# RTM_Connectors.net
KiCad netlist of a schematic drawn in Altium Designer
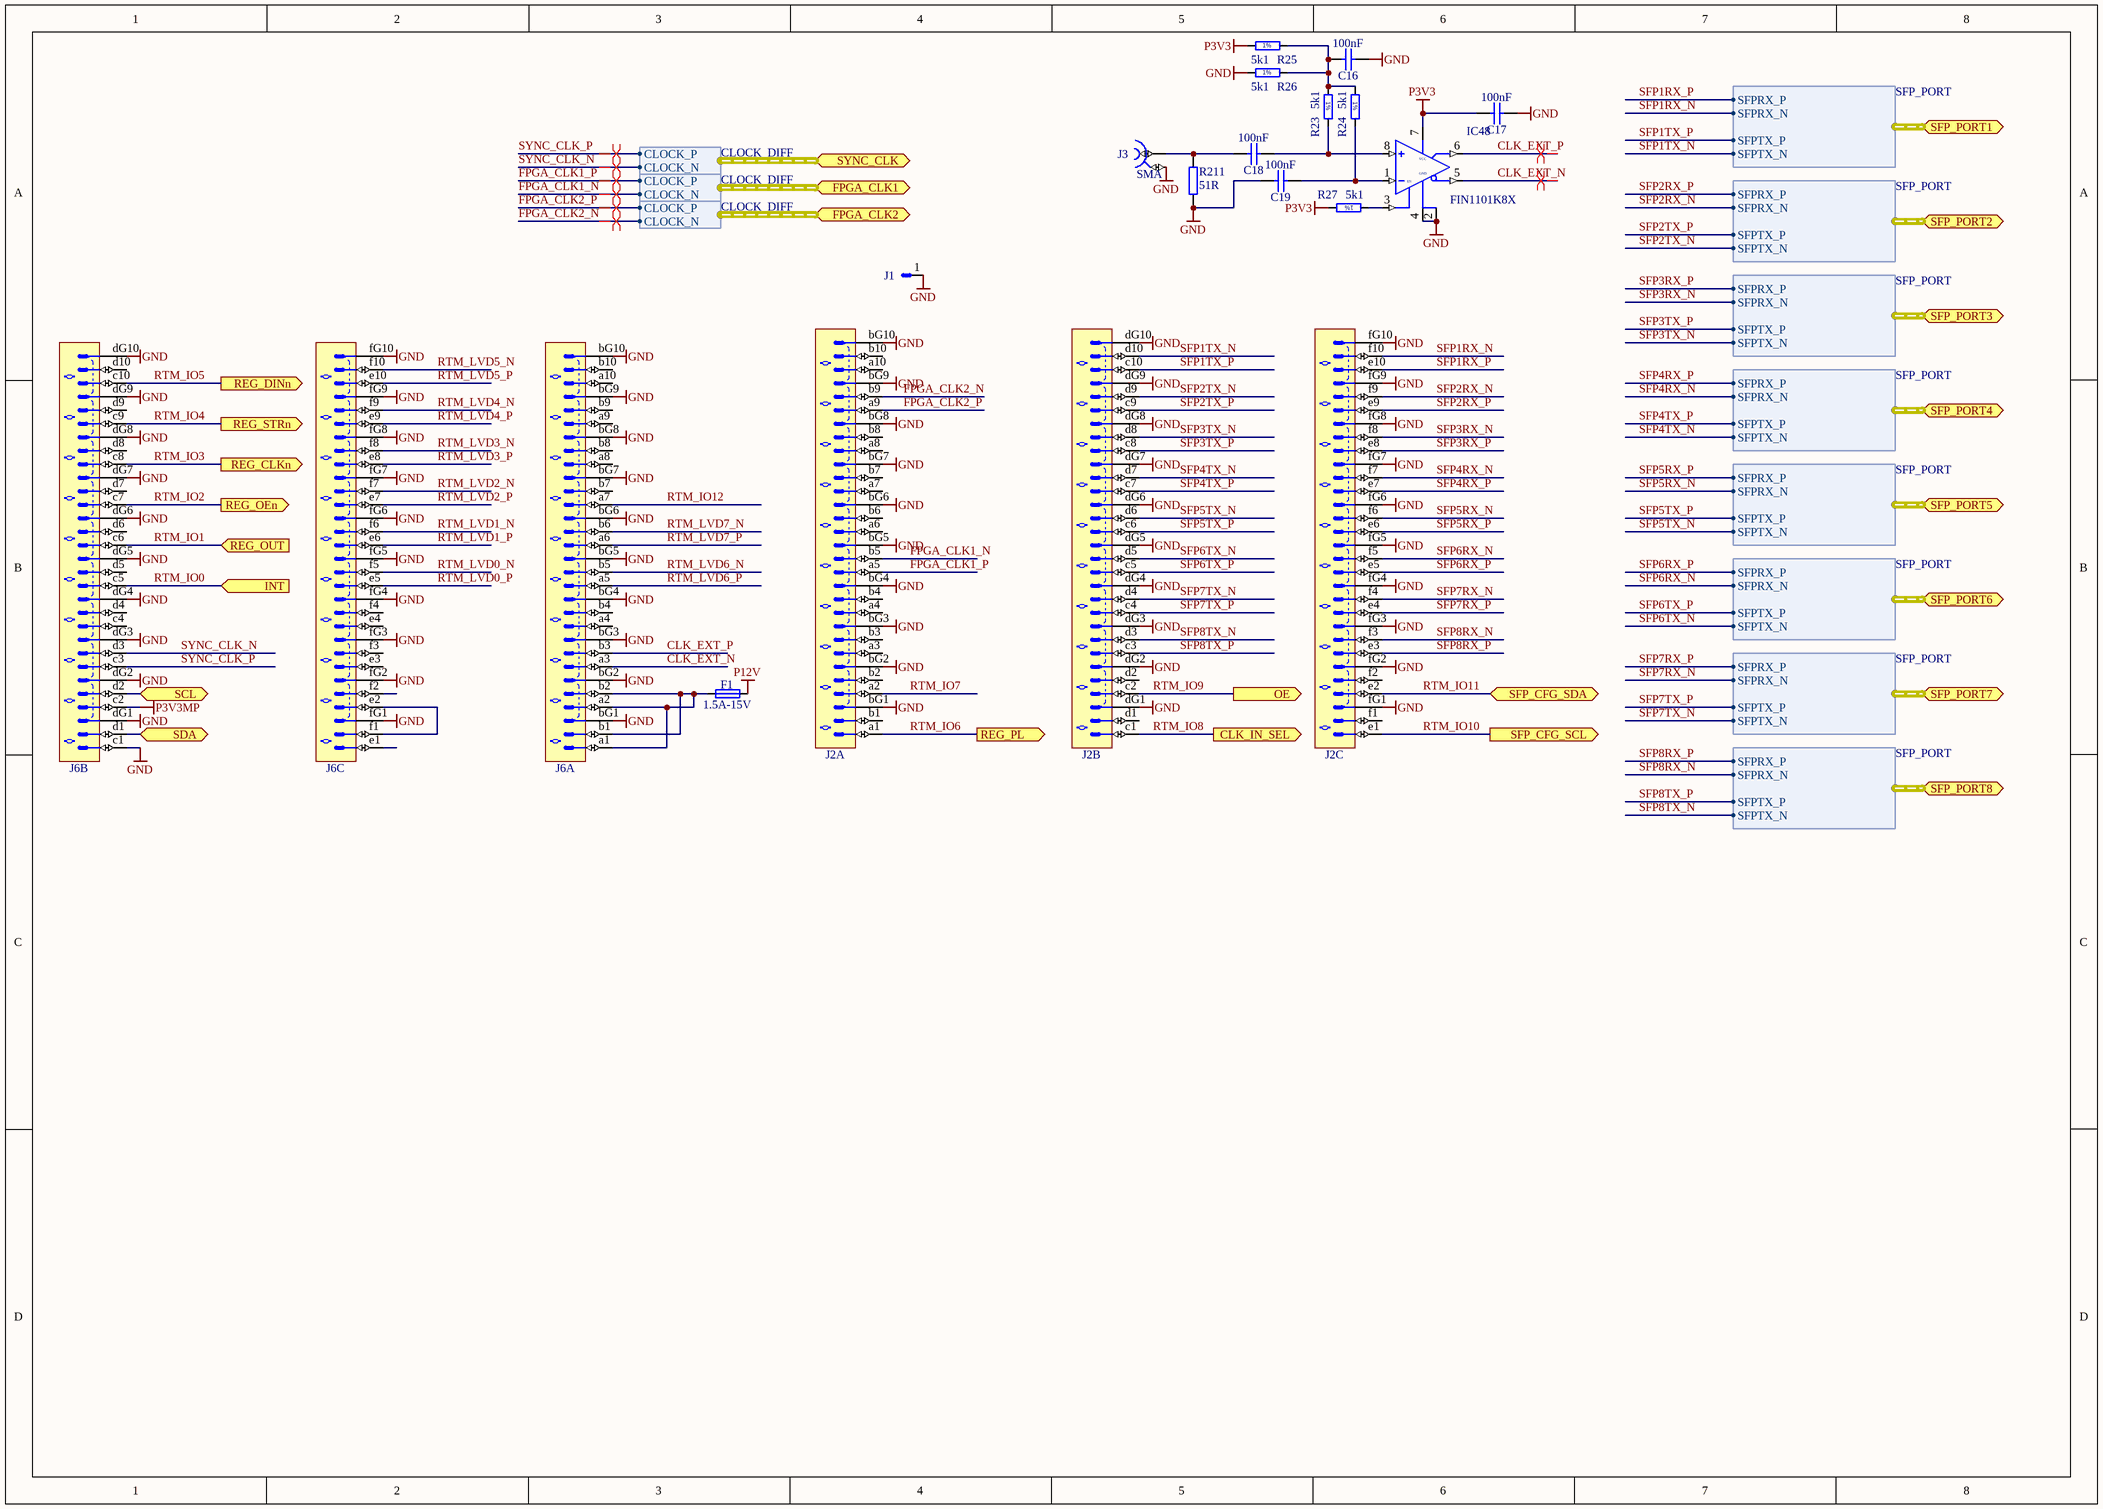
[diagram p0: RTM_Connectors.SchDoc]

(export (version "E")
  (design (tool "Eeschema 10.0.6"))
  (components
    (comp (ref "C16")
      (value "100nF")
      (footprint "CAPC1005X55N")
      (description "Non-polarised capacitor")
      (fields
        (field (name "PART NUMBER") "CC0402_100NF_16V_10%_X7R")
        (field (name "VOLTAGE") "16V")
        (field (name "AUTHOR") "CERN DEM JLC")
      )
      (libsource (lib "Capacitors") (part "Capacitor - non polarized"))
    )
    (comp (ref "C17")
      (value "100nF")
      (footprint "CAPC1005X55N")
      (description "Non-polarised capacitor")
      (fields
        (field (name "PART NUMBER") "CC0402_100NF_16V_10%_X7R")
        (field (name "VOLTAGE") "16V")
        (field (name "AUTHOR") "CERN DEM JLC")
      )
      (libsource (lib "Capacitors") (part "Capacitor - non polarized"))
    )
    (comp (ref "C18")
      (value "100nF")
      (footprint "CAPC1005X55N")
      (description "Non-polarised capacitor")
      (fields
        (field (name "PART NUMBER") "CC0402_100NF_16V_10%_X7R")
        (field (name "VOLTAGE") "16V")
        (field (name "AUTHOR") "CERN DEM JLC")
      )
      (libsource (lib "Capacitors") (part "Capacitor - non polarized"))
    )
    (comp (ref "C19")
      (value "100nF")
      (footprint "CAPC1005X55N")
      (description "Non-polarised capacitor")
      (fields
        (field (name "PART NUMBER") "CC0402_100NF_16V_10%_X7R")
        (field (name "VOLTAGE") "16V")
        (field (name "AUTHOR") "CERN DEM JLC")
      )
      (libsource (lib "Capacitors") (part "Capacitor - non polarized"))
    )
    (comp (ref "F1")
      (value "1.5A-15V")
      (footprint "FUSR_TYCO_SMD150F-2")
      (description "Fuse")
      (fields
        (field (name "PART NUMBER") "FUSR_TYCO_SMD150F-2")
        (field (name "MANUFACTURER") "TYCO ELECTRONICS")
        (field (name "AUTHOR") "CERN DEM JLC")
      )
      (libsource (lib "Eletro-mechanical") (part "Fuse"))
    )
    (comp (ref "IC48")
      (value "FIN1101K8X")
      (footprint "US8")
      (description "LVDS TO LVDS repeater3.3V")
      (libsource (lib "AMC_FMC_Carrier") (part "IFC_FIN1101K8X"))
    )
    (comp (ref "J1")
      (value "~")
      (footprint "TYCO_1469265-1")
      (description "Single Pin Male")
      (fields (field (name "PART NUMBER") "TYCO_1469265-1"))
      (libsource (lib "Connectors") (part "Single Pin Male"))
    )
    (comp (ref "J2")
      (value "~")
      (footprint "TYCO_6469183-1")
      (description "Connector 60 ATCA Male 30 Pairs (60 Signals) + 3x10 Ground")
      (fields (field (name "PART NUMBER") "TYCO_6469183-1"))
      (libsource (lib "Connectors") (part "Connector ATCA 60+30 Male"))
    )
    (comp (ref "J3")
      (value "SMA")
      (footprint "HUBER-SUHNER_85 SMA-50-0-101/111 NE")
      (fields
        (field (name "PART NUMBER") "HUBER-SUHNER_85_SMA-50-0-101/111_NE")
        (field (name "MANUFACTURER") "HUBER+SUHNER")
        (field (name "MANUFACTURER PART NUMBER") "85_SMA-50-0-101/111_NE")
        (field (name "AUTHOR") "CERN DEM JLC")
      )
      (libsource (lib "Connectors") (part "Coax_1Female_1Shield"))
    )
    (comp (ref "J6")
      (value "~")
      (footprint "TYCO_6469183-1")
      (description "Connector 60 ATCA Male 30 Pairs (60 Signals) + 3x10 Ground")
      (fields (field (name "PART NUMBER") "TYCO_6469183-1"))
      (libsource (lib "Connectors") (part "Connector ATCA 60+30 Male"))
    )
    (comp (ref "R23")
      (value "5k1")
      (footprint "RESC1608X55N")
      (description "Resistor - 1%")
      (fields
        (field (name "PART NUMBER") "R0603_5K1_1%_0.1W_100PPM")
        (field (name "POWER") "0.1W")
        (field (name "AUTHOR") "CERN DEM JLC")
      )
      (libsource (lib "Resistors") (part "Resistor - 1%"))
    )
    (comp (ref "R24")
      (value "5k1")
      (footprint "RESC1608X55N")
      (description "Resistor - 1%")
      (fields
        (field (name "PART NUMBER") "R0603_5K1_1%_0.1W_100PPM")
        (field (name "POWER") "0.1W")
        (field (name "AUTHOR") "CERN DEM JLC")
      )
      (libsource (lib "Resistors") (part "Resistor - 1%"))
    )
    (comp (ref "R25")
      (value "5k1")
      (footprint "RESC1608X55N")
      (description "Resistor - 1%")
      (fields
        (field (name "PART NUMBER") "R0603_5K1_1%_0.1W_100PPM")
        (field (name "POWER") "0.1W")
        (field (name "AUTHOR") "CERN DEM JLC")
      )
      (libsource (lib "Resistors") (part "Resistor - 1%"))
    )
    (comp (ref "R26")
      (value "5k1")
      (footprint "RESC1608X55N")
      (description "Resistor - 1%")
      (fields
        (field (name "PART NUMBER") "R0603_5K1_1%_0.1W_100PPM")
        (field (name "POWER") "0.1W")
        (field (name "AUTHOR") "CERN DEM JLC")
      )
      (libsource (lib "Resistors") (part "Resistor - 1%"))
    )
    (comp (ref "R27")
      (value "5k1")
      (footprint "RESC1608X55N")
      (description "Resistor - 1%")
      (fields
        (field (name "PART NUMBER") "R0603_5K1_1%_0.1W_100PPM")
        (field (name "POWER") "0.1W")
        (field (name "AUTHOR") "CERN DEM JLC")
      )
      (libsource (lib "Resistors") (part "Resistor - 1%"))
    )
    (comp (ref "R211")
      (value "51R")
      (footprint "0402R")
      (description "SMD Resistor")
      (libsource (lib "LIBRARY_SCH") (part "RES_0402"))
    )
  )
  (nets
    (net (code "3") (name "/CLK_EXT_N") (class "Default")
      (node (ref "IC48") (pin "5") (pinfunction "~{Q}_5") (pintype "output"))
      (node (ref "J6") (pin "a3") (pinfunction "a3_a3") (pintype "bidirectional"))
    )
    (net (code "4") (name "/CLK_EXT_P") (class "Default")
      (node (ref "IC48") (pin "6") (pinfunction "Q_6") (pintype "output"))
      (node (ref "J6") (pin "b3") (pinfunction "b3_b3") (pintype "bidirectional"))
    )
    (net (code "5") (name "/FPGA_CLK1_N") (class "Default")
      (node (ref "J2") (pin "b5") (pinfunction "b5_b5") (pintype "bidirectional"))
    )
    (net (code "6") (name "/FPGA_CLK1_P") (class "Default")
      (node (ref "J2") (pin "a5") (pinfunction "a5_a5") (pintype "bidirectional"))
    )
    (net (code "7") (name "/FPGA_CLK2_N") (class "Default")
      (node (ref "J2") (pin "b9") (pinfunction "b9_b9") (pintype "bidirectional"))
    )
    (net (code "8") (name "/FPGA_CLK2_P") (class "Default")
      (node (ref "J2") (pin "a9") (pinfunction "a9_a9") (pintype "bidirectional"))
    )
    (net (code "9") (name "/RTM_IO0") (class "Default")
      (node (ref "J6") (pin "c5") (pinfunction "c5_c5") (pintype "bidirectional"))
    )
    (net (code "10") (name "/RTM_IO1") (class "Default")
      (node (ref "J6") (pin "c6") (pinfunction "c6_c6") (pintype "bidirectional"))
    )
    (net (code "11") (name "/RTM_IO2") (class "Default")
      (node (ref "J6") (pin "c7") (pinfunction "c7_c7") (pintype "bidirectional"))
    )
    (net (code "12") (name "/RTM_IO3") (class "Default")
      (node (ref "J6") (pin "c8") (pinfunction "c8_c8") (pintype "bidirectional"))
    )
    (net (code "13") (name "/RTM_IO4") (class "Default")
      (node (ref "J6") (pin "c9") (pinfunction "c9_c9") (pintype "bidirectional"))
    )
    (net (code "14") (name "/RTM_IO5") (class "Default")
      (node (ref "J6") (pin "c10") (pinfunction "c10_c10") (pintype "bidirectional"))
    )
    (net (code "15") (name "/RTM_IO6") (class "Default")
      (node (ref "J2") (pin "a1") (pinfunction "a1_a1") (pintype "bidirectional"))
    )
    (net (code "16") (name "/RTM_IO7") (class "Default")
      (node (ref "J2") (pin "a2") (pinfunction "a2_a2") (pintype "bidirectional"))
    )
    (net (code "17") (name "/RTM_IO8") (class "Default")
      (node (ref "J2") (pin "c1") (pinfunction "c1_c1") (pintype "bidirectional"))
    )
    (net (code "18") (name "/RTM_IO9") (class "Default")
      (node (ref "J2") (pin "c2") (pinfunction "c2_c2") (pintype "bidirectional"))
    )
    (net (code "19") (name "/RTM_IO10") (class "Default")
      (node (ref "J2") (pin "e1") (pinfunction "e1_e1") (pintype "bidirectional"))
    )
    (net (code "20") (name "/RTM_IO11") (class "Default")
      (node (ref "J2") (pin "e2") (pinfunction "e2_e2") (pintype "bidirectional"))
    )
    (net (code "21") (name "/RTM_IO12") (class "Default")
      (node (ref "J6") (pin "a7") (pinfunction "a7_a7") (pintype "bidirectional"))
    )
    (net (code "22") (name "/RTM_LVD0_N") (class "Default")
      (node (ref "J6") (pin "f5") (pinfunction "f5_f5") (pintype "bidirectional"))
    )
    (net (code "23") (name "/RTM_LVD0_P") (class "Default")
      (node (ref "J6") (pin "e5") (pinfunction "e5_e5") (pintype "bidirectional"))
    )
    (net (code "24") (name "/RTM_LVD1_N") (class "Default")
      (node (ref "J6") (pin "f6") (pinfunction "f6_f6") (pintype "bidirectional"))
    )
    (net (code "25") (name "/RTM_LVD1_P") (class "Default")
      (node (ref "J6") (pin "e6") (pinfunction "e6_e6") (pintype "bidirectional"))
    )
    (net (code "26") (name "/RTM_LVD2_N") (class "Default")
      (node (ref "J6") (pin "f7") (pinfunction "f7_f7") (pintype "bidirectional"))
    )
    (net (code "27") (name "/RTM_LVD2_P") (class "Default")
      (node (ref "J6") (pin "e7") (pinfunction "e7_e7") (pintype "bidirectional"))
    )
    (net (code "28") (name "/RTM_LVD3_N") (class "Default")
      (node (ref "J6") (pin "f8") (pinfunction "f8_f8") (pintype "bidirectional"))
    )
    (net (code "29") (name "/RTM_LVD3_P") (class "Default")
      (node (ref "J6") (pin "e8") (pinfunction "e8_e8") (pintype "bidirectional"))
    )
    (net (code "30") (name "/RTM_LVD4_N") (class "Default")
      (node (ref "J6") (pin "f9") (pinfunction "f9_f9") (pintype "bidirectional"))
    )
    (net (code "31") (name "/RTM_LVD4_P") (class "Default")
      (node (ref "J6") (pin "e9") (pinfunction "e9_e9") (pintype "bidirectional"))
    )
    (net (code "32") (name "/RTM_LVD5_N") (class "Default")
      (node (ref "J6") (pin "f10") (pinfunction "f10_f10") (pintype "bidirectional"))
    )
    (net (code "33") (name "/RTM_LVD5_P") (class "Default")
      (node (ref "J6") (pin "e10") (pinfunction "e10_e10") (pintype "bidirectional"))
    )
    (net (code "34") (name "/RTM_LVD6_N") (class "Default")
      (node (ref "J6") (pin "b5") (pinfunction "b5_b5") (pintype "bidirectional"))
    )
    (net (code "35") (name "/RTM_LVD6_P") (class "Default")
      (node (ref "J6") (pin "a5") (pinfunction "a5_a5") (pintype "bidirectional"))
    )
    (net (code "36") (name "/RTM_LVD7_N") (class "Default")
      (node (ref "J6") (pin "b6") (pinfunction "b6_b6") (pintype "bidirectional"))
    )
    (net (code "37") (name "/RTM_LVD7_P") (class "Default")
      (node (ref "J6") (pin "a6") (pinfunction "a6_a6") (pintype "bidirectional"))
    )
    (net (code "38") (name "/SCL") (class "Default")
      (node (ref "J6") (pin "d2") (pinfunction "d2_d2") (pintype "bidirectional"))
    )
    (net (code "39") (name "/SDA") (class "Default")
      (node (ref "J6") (pin "d1") (pinfunction "d1_d1") (pintype "bidirectional"))
    )
    (net (code "40") (name "/SFP1RX_N") (class "Default")
      (node (ref "J2") (pin "f10") (pinfunction "f10_f10") (pintype "bidirectional"))
    )
    (net (code "41") (name "/SFP1RX_P") (class "Default")
      (node (ref "J2") (pin "e10") (pinfunction "e10_e10") (pintype "bidirectional"))
    )
    (net (code "42") (name "/SFP1TX_N") (class "Default")
      (node (ref "J2") (pin "d10") (pinfunction "d10_d10") (pintype "bidirectional"))
    )
    (net (code "43") (name "/SFP1TX_P") (class "Default")
      (node (ref "J2") (pin "c10") (pinfunction "c10_c10") (pintype "bidirectional"))
    )
    (net (code "44") (name "/SFP2RX_N") (class "Default")
      (node (ref "J2") (pin "f9") (pinfunction "f9_f9") (pintype "bidirectional"))
    )
    (net (code "45") (name "/SFP2RX_P") (class "Default")
      (node (ref "J2") (pin "e9") (pinfunction "e9_e9") (pintype "bidirectional"))
    )
    (net (code "46") (name "/SFP2TX_N") (class "Default")
      (node (ref "J2") (pin "d9") (pinfunction "d9_d9") (pintype "bidirectional"))
    )
    (net (code "47") (name "/SFP2TX_P") (class "Default")
      (node (ref "J2") (pin "c9") (pinfunction "c9_c9") (pintype "bidirectional"))
    )
    (net (code "48") (name "/SFP3RX_N") (class "Default")
      (node (ref "J2") (pin "f8") (pinfunction "f8_f8") (pintype "bidirectional"))
    )
    (net (code "49") (name "/SFP3RX_P") (class "Default")
      (node (ref "J2") (pin "e8") (pinfunction "e8_e8") (pintype "bidirectional"))
    )
    (net (code "50") (name "/SFP3TX_N") (class "Default")
      (node (ref "J2") (pin "d8") (pinfunction "d8_d8") (pintype "bidirectional"))
    )
    (net (code "51") (name "/SFP3TX_P") (class "Default")
      (node (ref "J2") (pin "c8") (pinfunction "c8_c8") (pintype "bidirectional"))
    )
    (net (code "52") (name "/SFP4RX_N") (class "Default")
      (node (ref "J2") (pin "f7") (pinfunction "f7_f7") (pintype "bidirectional"))
    )
    (net (code "53") (name "/SFP4RX_P") (class "Default")
      (node (ref "J2") (pin "e7") (pinfunction "e7_e7") (pintype "bidirectional"))
    )
    (net (code "54") (name "/SFP4TX_N") (class "Default")
      (node (ref "J2") (pin "d7") (pinfunction "d7_d7") (pintype "bidirectional"))
    )
    (net (code "55") (name "/SFP4TX_P") (class "Default")
      (node (ref "J2") (pin "c7") (pinfunction "c7_c7") (pintype "bidirectional"))
    )
    (net (code "56") (name "/SFP5RX_N") (class "Default")
      (node (ref "J2") (pin "f6") (pinfunction "f6_f6") (pintype "bidirectional"))
    )
    (net (code "57") (name "/SFP5RX_P") (class "Default")
      (node (ref "J2") (pin "e6") (pinfunction "e6_e6") (pintype "bidirectional"))
    )
    (net (code "58") (name "/SFP5TX_N") (class "Default")
      (node (ref "J2") (pin "d6") (pinfunction "d6_d6") (pintype "bidirectional"))
    )
    (net (code "59") (name "/SFP5TX_P") (class "Default")
      (node (ref "J2") (pin "c6") (pinfunction "c6_c6") (pintype "bidirectional"))
    )
    (net (code "60") (name "/SFP6RX_N") (class "Default")
      (node (ref "J2") (pin "f5") (pinfunction "f5_f5") (pintype "bidirectional"))
    )
    (net (code "61") (name "/SFP6RX_P") (class "Default")
      (node (ref "J2") (pin "e5") (pinfunction "e5_e5") (pintype "bidirectional"))
    )
    (net (code "62") (name "/SFP6TX_N") (class "Default")
      (node (ref "J2") (pin "d5") (pinfunction "d5_d5") (pintype "bidirectional"))
    )
    (net (code "63") (name "/SFP6TX_P") (class "Default")
      (node (ref "J2") (pin "c5") (pinfunction "c5_c5") (pintype "bidirectional"))
    )
    (net (code "64") (name "/SFP7RX_N") (class "Default")
      (node (ref "J2") (pin "f4") (pinfunction "f4_f4") (pintype "bidirectional"))
    )
    (net (code "65") (name "/SFP7RX_P") (class "Default")
      (node (ref "J2") (pin "e4") (pinfunction "e4_e4") (pintype "bidirectional"))
    )
    (net (code "66") (name "/SFP7TX_N") (class "Default")
      (node (ref "J2") (pin "d4") (pinfunction "d4_d4") (pintype "bidirectional"))
    )
    (net (code "67") (name "/SFP7TX_P") (class "Default")
      (node (ref "J2") (pin "c4") (pinfunction "c4_c4") (pintype "bidirectional"))
    )
    (net (code "68") (name "/SFP8RX_N") (class "Default")
      (node (ref "J2") (pin "f3") (pinfunction "f3_f3") (pintype "bidirectional"))
    )
    (net (code "69") (name "/SFP8RX_P") (class "Default")
      (node (ref "J2") (pin "e3") (pinfunction "e3_e3") (pintype "bidirectional"))
    )
    (net (code "70") (name "/SFP8TX_N") (class "Default")
      (node (ref "J2") (pin "d3") (pinfunction "d3_d3") (pintype "bidirectional"))
    )
    (net (code "71") (name "/SFP8TX_P") (class "Default")
      (node (ref "J2") (pin "c3") (pinfunction "c3_c3") (pintype "bidirectional"))
    )
    (net (code "72") (name "/SYNC_CLK_N") (class "Default")
      (node (ref "J6") (pin "d3") (pinfunction "d3_d3") (pintype "bidirectional"))
    )
    (net (code "73") (name "/SYNC_CLK_P") (class "Default")
      (node (ref "J6") (pin "c3") (pinfunction "c3_c3") (pintype "bidirectional"))
    )
    (net (code "76") (name "GND") (class "Default")
      (node (ref "C16") (pin "2") (pinfunction "2_2") (pintype "passive"))
      (node (ref "C17") (pin "2") (pinfunction "2_2") (pintype "passive"))
      (node (ref "C19") (pin "1") (pinfunction "1_1") (pintype "passive"))
      (node (ref "IC48") (pin "2") (pinfunction "GND_2") (pintype "power_in"))
      (node (ref "IC48") (pin "4") (pinfunction "GND_4") (pintype "power_in"))
      (node (ref "J1") (pin "1") (pinfunction "1_1") (pintype "bidirectional"))
      (node (ref "J2") (pin "bG1") (pinfunction "bG1_bG1") (pintype "power_in"))
      (node (ref "J2") (pin "bG10") (pinfunction "bG10_bG10") (pintype "power_in"))
      (node (ref "J2") (pin "bG2") (pinfunction "bG2_bG2") (pintype "power_in"))
      (node (ref "J2") (pin "bG3") (pinfunction "bG3_bG3") (pintype "power_in"))
      (node (ref "J2") (pin "bG4") (pinfunction "bG4_bG4") (pintype "power_in"))
      (node (ref "J2") (pin "bG5") (pinfunction "bG5_bG5") (pintype "power_in"))
      (node (ref "J2") (pin "bG6") (pinfunction "bG6_bG6") (pintype "power_in"))
      (node (ref "J2") (pin "bG7") (pinfunction "bG7_bG7") (pintype "power_in"))
      (node (ref "J2") (pin "bG8") (pinfunction "bG8_bG8") (pintype "power_in"))
      (node (ref "J2") (pin "bG9") (pinfunction "bG9_bG9") (pintype "power_in"))
      (node (ref "J2") (pin "dG1") (pinfunction "dG1_dG1") (pintype "power_in"))
      (node (ref "J2") (pin "dG10") (pinfunction "dG10_dG10") (pintype "power_in"))
      (node (ref "J2") (pin "dG2") (pinfunction "dG2_dG2") (pintype "power_in"))
      (node (ref "J2") (pin "dG3") (pinfunction "dG3_dG3") (pintype "power_in"))
      (node (ref "J2") (pin "dG4") (pinfunction "dG4_dG4") (pintype "power_in"))
      (node (ref "J2") (pin "dG5") (pinfunction "dG5_dG5") (pintype "power_in"))
      (node (ref "J2") (pin "dG6") (pinfunction "dG6_dG6") (pintype "power_in"))
      (node (ref "J2") (pin "dG7") (pinfunction "dG7_dG7") (pintype "power_in"))
      (node (ref "J2") (pin "dG8") (pinfunction "dG8_dG8") (pintype "power_in"))
      (node (ref "J2") (pin "dG9") (pinfunction "dG9_dG9") (pintype "power_in"))
      (node (ref "J2") (pin "fG1") (pinfunction "fG1_fG1") (pintype "power_in"))
      (node (ref "J2") (pin "fG10") (pinfunction "fG10_fG10") (pintype "power_in"))
      (node (ref "J2") (pin "fG2") (pinfunction "fG2_fG2") (pintype "power_in"))
      (node (ref "J2") (pin "fG3") (pinfunction "fG3_fG3") (pintype "power_in"))
      (node (ref "J2") (pin "fG4") (pinfunction "fG4_fG4") (pintype "power_in"))
      (node (ref "J2") (pin "fG5") (pinfunction "fG5_fG5") (pintype "power_in"))
      (node (ref "J2") (pin "fG6") (pinfunction "fG6_fG6") (pintype "power_in"))
      (node (ref "J2") (pin "fG7") (pinfunction "fG7_fG7") (pintype "power_in"))
      (node (ref "J2") (pin "fG8") (pinfunction "fG8_fG8") (pintype "power_in"))
      (node (ref "J2") (pin "fG9") (pinfunction "fG9_fG9") (pintype "power_in"))
      (node (ref "J3") (pin "2") (pinfunction "2_2") (pintype "bidirectional"))
      (node (ref "J6") (pin "bG1") (pinfunction "bG1_bG1") (pintype "power_in"))
      (node (ref "J6") (pin "bG10") (pinfunction "bG10_bG10") (pintype "power_in"))
      (node (ref "J6") (pin "bG2") (pinfunction "bG2_bG2") (pintype "power_in"))
      (node (ref "J6") (pin "bG3") (pinfunction "bG3_bG3") (pintype "power_in"))
      (node (ref "J6") (pin "bG4") (pinfunction "bG4_bG4") (pintype "power_in"))
      (node (ref "J6") (pin "bG5") (pinfunction "bG5_bG5") (pintype "power_in"))
      (node (ref "J6") (pin "bG6") (pinfunction "bG6_bG6") (pintype "power_in"))
      (node (ref "J6") (pin "bG7") (pinfunction "bG7_bG7") (pintype "power_in"))
      (node (ref "J6") (pin "bG8") (pinfunction "bG8_bG8") (pintype "power_in"))
      (node (ref "J6") (pin "bG9") (pinfunction "bG9_bG9") (pintype "power_in"))
      (node (ref "J6") (pin "c1") (pinfunction "c1_c1") (pintype "bidirectional"))
      (node (ref "J6") (pin "dG1") (pinfunction "dG1_dG1") (pintype "power_in"))
      (node (ref "J6") (pin "dG10") (pinfunction "dG10_dG10") (pintype "power_in"))
      (node (ref "J6") (pin "dG2") (pinfunction "dG2_dG2") (pintype "power_in"))
      (node (ref "J6") (pin "dG3") (pinfunction "dG3_dG3") (pintype "power_in"))
      (node (ref "J6") (pin "dG4") (pinfunction "dG4_dG4") (pintype "power_in"))
      (node (ref "J6") (pin "dG5") (pinfunction "dG5_dG5") (pintype "power_in"))
      (node (ref "J6") (pin "dG6") (pinfunction "dG6_dG6") (pintype "power_in"))
      (node (ref "J6") (pin "dG7") (pinfunction "dG7_dG7") (pintype "power_in"))
      (node (ref "J6") (pin "dG8") (pinfunction "dG8_dG8") (pintype "power_in"))
      (node (ref "J6") (pin "dG9") (pinfunction "dG9_dG9") (pintype "power_in"))
      (node (ref "J6") (pin "fG1") (pinfunction "fG1_fG1") (pintype "power_in"))
      (node (ref "J6") (pin "fG10") (pinfunction "fG10_fG10") (pintype "power_in"))
      (node (ref "J6") (pin "fG2") (pinfunction "fG2_fG2") (pintype "power_in"))
      (node (ref "J6") (pin "fG3") (pinfunction "fG3_fG3") (pintype "power_in"))
      (node (ref "J6") (pin "fG4") (pinfunction "fG4_fG4") (pintype "power_in"))
      (node (ref "J6") (pin "fG5") (pinfunction "fG5_fG5") (pintype "power_in"))
      (node (ref "J6") (pin "fG6") (pinfunction "fG6_fG6") (pintype "power_in"))
      (node (ref "J6") (pin "fG7") (pinfunction "fG7_fG7") (pintype "power_in"))
      (node (ref "J6") (pin "fG8") (pinfunction "fG8_fG8") (pintype "power_in"))
      (node (ref "J6") (pin "fG9") (pinfunction "fG9_fG9") (pintype "power_in"))
      (node (ref "R211") (pin "2") (pinfunction "2_2") (pintype "passive"))
      (node (ref "R26") (pin "1") (pinfunction "1_1") (pintype "passive"))
    )
    (net (code "77") (name "Net-(C16-Pad1)") (class "Default")
      (node (ref "C16") (pin "1") (pinfunction "1_1") (pintype "passive"))
      (node (ref "R23") (pin "1") (pinfunction "1_1") (pintype "passive"))
      (node (ref "R24") (pin "1") (pinfunction "1_1") (pintype "passive"))
      (node (ref "R25") (pin "2") (pinfunction "2_2") (pintype "passive"))
      (node (ref "R26") (pin "2") (pinfunction "2_2") (pintype "passive"))
    )
    (net (code "78") (name "Net-(C18-Pad1)") (class "Default")
      (node (ref "C18") (pin "1") (pinfunction "1_1") (pintype "passive"))
      (node (ref "J3") (pin "1") (pinfunction "1_1") (pintype "bidirectional"))
      (node (ref "R211") (pin "1") (pinfunction "1_1") (pintype "passive"))
    )
    (net (code "79") (name "Net-(C18-Pad2)") (class "Default")
      (node (ref "C18") (pin "2") (pinfunction "2_2") (pintype "passive"))
      (node (ref "IC48") (pin "8") (pinfunction "IN_8") (pintype "input"))
      (node (ref "R23") (pin "2") (pinfunction "2_2") (pintype "passive"))
    )
    (net (code "80") (name "Net-(C19-Pad2)") (class "Default")
      (node (ref "C19") (pin "2") (pinfunction "2_2") (pintype "passive"))
      (node (ref "IC48") (pin "1") (pinfunction "IN_1") (pintype "input"))
      (node (ref "R24") (pin "2") (pinfunction "2_2") (pintype "passive"))
    )
    (net (code "81") (name "Net-(F1-Pad1)") (class "Default")
      (node (ref "F1") (pin "1") (pinfunction "1_1") (pintype "passive"))
      (node (ref "J6") (pin "a1") (pinfunction "a1_a1") (pintype "bidirectional"))
      (node (ref "J6") (pin "a2") (pinfunction "a2_a2") (pintype "bidirectional"))
      (node (ref "J6") (pin "b1") (pinfunction "b1_b1") (pintype "bidirectional"))
      (node (ref "J6") (pin "b2") (pinfunction "b2_b2") (pintype "bidirectional"))
    )
    (net (code "82") (name "Net-(IC48-EN)") (class "Default")
      (node (ref "IC48") (pin "3") (pinfunction "EN_3") (pintype "input"))
      (node (ref "R27") (pin "1") (pinfunction "1_1") (pintype "passive"))
    )
    (net (code "83") (name "Net-(J6-Pade2)") (class "Default")
      (node (ref "J6") (pin "e2") (pinfunction "e2_e2") (pintype "bidirectional"))
      (node (ref "J6") (pin "f1") (pinfunction "f1_f1") (pintype "bidirectional"))
    )
    (net (code "84") (name "P3V3") (class "Default")
      (node (ref "C17") (pin "1") (pinfunction "1_1") (pintype "passive"))
      (node (ref "IC48") (pin "7") (pinfunction "VCC_7") (pintype "power_in"))
      (node (ref "R25") (pin "1") (pinfunction "1_1") (pintype "passive"))
      (node (ref "R27") (pin "2") (pinfunction "2_2") (pintype "passive"))
    )
    (net (code "85") (name "P3V3MP") (class "Default")
      (node (ref "J6") (pin "c2") (pinfunction "c2_c2") (pintype "bidirectional"))
    )
    (net (code "86") (name "P12V") (class "Default")
      (node (ref "F1") (pin "2") (pinfunction "2_2") (pintype "passive"))
    )
    (net (code "87") (name "unconnected-(J2-Pada3)") (class "Default")
      (node (ref "J2") (pin "a3") (pinfunction "a3_a3") (pintype "bidirectional"))
    )
    (net (code "88") (name "unconnected-(J2-Pada4)") (class "Default")
      (node (ref "J2") (pin "a4") (pinfunction "a4_a4") (pintype "bidirectional"))
    )
    (net (code "89") (name "unconnected-(J2-Pada6)") (class "Default")
      (node (ref "J2") (pin "a6") (pinfunction "a6_a6") (pintype "bidirectional"))
    )
    (net (code "90") (name "unconnected-(J2-Pada7)") (class "Default")
      (node (ref "J2") (pin "a7") (pinfunction "a7_a7") (pintype "bidirectional"))
    )
    (net (code "91") (name "unconnected-(J2-Pada8)") (class "Default")
      (node (ref "J2") (pin "a8") (pinfunction "a8_a8") (pintype "bidirectional"))
    )
    (net (code "92") (name "unconnected-(J2-Pada10)") (class "Default")
      (node (ref "J2") (pin "a10") (pinfunction "a10_a10") (pintype "bidirectional"))
    )
    (net (code "93") (name "unconnected-(J2-Padb1)") (class "Default")
      (node (ref "J2") (pin "b1") (pinfunction "b1_b1") (pintype "bidirectional"))
    )
    (net (code "94") (name "unconnected-(J2-Padb2)") (class "Default")
      (node (ref "J2") (pin "b2") (pinfunction "b2_b2") (pintype "bidirectional"))
    )
    (net (code "95") (name "unconnected-(J2-Padb3)") (class "Default")
      (node (ref "J2") (pin "b3") (pinfunction "b3_b3") (pintype "bidirectional"))
    )
    (net (code "96") (name "unconnected-(J2-Padb4)") (class "Default")
      (node (ref "J2") (pin "b4") (pinfunction "b4_b4") (pintype "bidirectional"))
    )
    (net (code "97") (name "unconnected-(J2-Padb6)") (class "Default")
      (node (ref "J2") (pin "b6") (pinfunction "b6_b6") (pintype "bidirectional"))
    )
    (net (code "98") (name "unconnected-(J2-Padb7)") (class "Default")
      (node (ref "J2") (pin "b7") (pinfunction "b7_b7") (pintype "bidirectional"))
    )
    (net (code "99") (name "unconnected-(J2-Padb8)") (class "Default")
      (node (ref "J2") (pin "b8") (pinfunction "b8_b8") (pintype "bidirectional"))
    )
    (net (code "100") (name "unconnected-(J2-Padb10)") (class "Default")
      (node (ref "J2") (pin "b10") (pinfunction "b10_b10") (pintype "bidirectional"))
    )
    (net (code "101") (name "unconnected-(J2-Padd1)") (class "Default")
      (node (ref "J2") (pin "d1") (pinfunction "d1_d1") (pintype "bidirectional"))
    )
    (net (code "102") (name "unconnected-(J2-Padd2)") (class "Default")
      (node (ref "J2") (pin "d2") (pinfunction "d2_d2") (pintype "bidirectional"))
    )
    (net (code "103") (name "unconnected-(J2-Padf1)") (class "Default")
      (node (ref "J2") (pin "f1") (pinfunction "f1_f1") (pintype "bidirectional"))
    )
    (net (code "104") (name "unconnected-(J2-Padf2)") (class "Default")
      (node (ref "J2") (pin "f2") (pinfunction "f2_f2") (pintype "bidirectional"))
    )
    (net (code "105") (name "unconnected-(J6-Pada4)") (class "Default")
      (node (ref "J6") (pin "a4") (pinfunction "a4_a4") (pintype "bidirectional"))
    )
    (net (code "106") (name "unconnected-(J6-Pada8)") (class "Default")
      (node (ref "J6") (pin "a8") (pinfunction "a8_a8") (pintype "bidirectional"))
    )
    (net (code "107") (name "unconnected-(J6-Pada9)") (class "Default")
      (node (ref "J6") (pin "a9") (pinfunction "a9_a9") (pintype "bidirectional"))
    )
    (net (code "108") (name "unconnected-(J6-Pada10)") (class "Default")
      (node (ref "J6") (pin "a10") (pinfunction "a10_a10") (pintype "bidirectional"))
    )
    (net (code "109") (name "unconnected-(J6-Padb4)") (class "Default")
      (node (ref "J6") (pin "b4") (pinfunction "b4_b4") (pintype "bidirectional"))
    )
    (net (code "110") (name "unconnected-(J6-Padb7)") (class "Default")
      (node (ref "J6") (pin "b7") (pinfunction "b7_b7") (pintype "bidirectional"))
    )
    (net (code "111") (name "unconnected-(J6-Padb8)") (class "Default")
      (node (ref "J6") (pin "b8") (pinfunction "b8_b8") (pintype "bidirectional"))
    )
    (net (code "112") (name "unconnected-(J6-Padb9)") (class "Default")
      (node (ref "J6") (pin "b9") (pinfunction "b9_b9") (pintype "bidirectional"))
    )
    (net (code "113") (name "unconnected-(J6-Padb10)") (class "Default")
      (node (ref "J6") (pin "b10") (pinfunction "b10_b10") (pintype "bidirectional"))
    )
    (net (code "114") (name "unconnected-(J6-Padc4)") (class "Default")
      (node (ref "J6") (pin "c4") (pinfunction "c4_c4") (pintype "bidirectional"))
    )
    (net (code "115") (name "unconnected-(J6-Padd4)") (class "Default")
      (node (ref "J6") (pin "d4") (pinfunction "d4_d4") (pintype "bidirectional"))
    )
    (net (code "116") (name "unconnected-(J6-Padd5)") (class "Default")
      (node (ref "J6") (pin "d5") (pinfunction "d5_d5") (pintype "bidirectional"))
    )
    (net (code "117") (name "unconnected-(J6-Padd6)") (class "Default")
      (node (ref "J6") (pin "d6") (pinfunction "d6_d6") (pintype "bidirectional"))
    )
    (net (code "118") (name "unconnected-(J6-Padd7)") (class "Default")
      (node (ref "J6") (pin "d7") (pinfunction "d7_d7") (pintype "bidirectional"))
    )
    (net (code "119") (name "unconnected-(J6-Padd8)") (class "Default")
      (node (ref "J6") (pin "d8") (pinfunction "d8_d8") (pintype "bidirectional"))
    )
    (net (code "120") (name "unconnected-(J6-Padd9)") (class "Default")
      (node (ref "J6") (pin "d9") (pinfunction "d9_d9") (pintype "bidirectional"))
    )
    (net (code "121") (name "unconnected-(J6-Padd10)") (class "Default")
      (node (ref "J6") (pin "d10") (pinfunction "d10_d10") (pintype "bidirectional"))
    )
    (net (code "122") (name "unconnected-(J6-Pade1)") (class "Default")
      (node (ref "J6") (pin "e1") (pinfunction "e1_e1") (pintype "bidirectional"))
    )
    (net (code "123") (name "unconnected-(J6-Pade3)") (class "Default")
      (node (ref "J6") (pin "e3") (pinfunction "e3_e3") (pintype "bidirectional"))
    )
    (net (code "124") (name "unconnected-(J6-Pade4)") (class "Default")
      (node (ref "J6") (pin "e4") (pinfunction "e4_e4") (pintype "bidirectional"))
    )
    (net (code "125") (name "unconnected-(J6-Padf2)") (class "Default")
      (node (ref "J6") (pin "f2") (pinfunction "f2_f2") (pintype "bidirectional"))
    )
    (net (code "126") (name "unconnected-(J6-Padf3)") (class "Default")
      (node (ref "J6") (pin "f3") (pinfunction "f3_f3") (pintype "bidirectional"))
    )
    (net (code "127") (name "unconnected-(J6-Padf4)") (class "Default")
      (node (ref "J6") (pin "f4") (pinfunction "f4_f4") (pintype "bidirectional"))
    )
  )
)
